# MAGI_sUSBMeter.net
KiCad netlist of a schematic drawn in Altium Designer
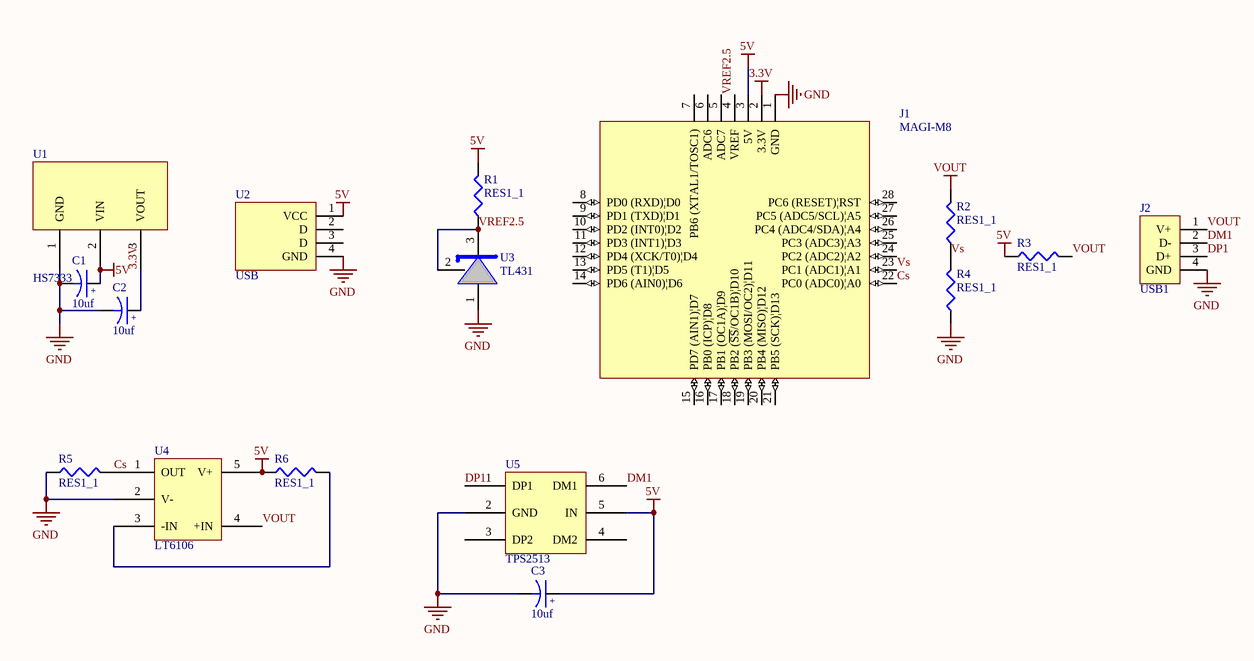
[diagram p0: MAGI'sUSBMeter.SchDoc]

(export (version "E")
  (design (tool "Eeschema 10.0.6"))
  (components
    (comp (ref "C1")
      (value "10uf")
      (footprint "6-0805_N")
      (description "Capacitor")
      (libsource (lib "电容器") (part "CAPACITOR POL"))
    )
    (comp (ref "C2")
      (value "10uf")
      (footprint "6-0805_N")
      (description "Capacitor")
      (libsource (lib "电容器") (part "CAPACITOR POL"))
    )
    (comp (ref "C3")
      (value "10uf")
      (footprint "6-0805_N")
      (description "Capacitor")
      (libsource (lib "电容器") (part "CAPACITOR POL"))
    )
    (comp (ref "J1") (value "MAGI-M8") (footprint "MAGI-M8") (libsource (lib "MAGI-M8") (part "MAGI-M8")))
    (comp (ref "J2") (value "USB1") (footprint "USB-04A") (libsource (lib "USB接口") (part "USB1")))
    (comp (ref "R1") (value "RES1_1") (footprint "6-0805_N") (libsource (lib "电阻器") (part "RES1_1")))
    (comp (ref "R2") (value "RES1_1") (footprint "6-0805_N") (libsource (lib "电阻器") (part "RES1_1")))
    (comp (ref "R3") (value "RES1_1") (footprint "2512") (libsource (lib "电阻器") (part "RES1_1")))
    (comp (ref "R4") (value "RES1_1") (footprint "6-0805_N") (libsource (lib "电阻器") (part "RES1_1")))
    (comp (ref "R5") (value "RES1_1") (footprint "6-0805_N") (libsource (lib "电阻器") (part "RES1_1")))
    (comp (ref "R6") (value "RES1_1") (footprint "6-0805_N") (libsource (lib "电阻器") (part "RES1_1")))
    (comp (ref "U1") (value "HS7333") (footprint "HS7333") (libsource (lib "PMIC") (part "HS7333")))
    (comp (ref "U2") (value "USB") (footprint "MicroUSB") (libsource (lib "USB接口") (part "USB")))
    (comp (ref "U3") (value "TL431") (footprint "SOT23_N") (libsource (lib "汇总") (part "TL431")))
    (comp (ref "U4") (value "LT6106") (footprint "LM2731") (libsource (lib "PMIC") (part "LT6106")))
    (comp (ref "U5") (value "TPS2513") (footprint "TPS2513") (libsource (lib "PMIC") (part "TPS2513")))
  )
  (nets
    (net (code "1") (name "/Cs") (class "Default")
      (node (ref "J1") (pin "22") (pinfunction "PC0_(ADC0)¦A0_22") (pintype "bidirectional"))
      (node (ref "R5") (pin "2") (pinfunction "2_2") (pintype "passive"))
      (node (ref "U4") (pin "1") (pinfunction "OUT_1") (pintype "passive"))
    )
    (net (code "2") (name "/DM1") (class "Default")
      (node (ref "J2") (pin "2") (pinfunction "D-_2") (pintype "passive"))
      (node (ref "U5") (pin "6") (pinfunction "DM1_6") (pintype "passive"))
    )
    (net (code "3") (name "/DP1") (class "Default")
      (node (ref "J2") (pin "3") (pinfunction "D+_3") (pintype "passive"))
      (node (ref "U5") (pin "1") (pinfunction "DP1_1") (pintype "passive"))
    )
    (net (code "4") (name "/VREF2.5") (class "Default")
      (node (ref "J1") (pin "4") (pinfunction "VREF_4") (pintype "passive"))
      (node (ref "R1") (pin "1") (pinfunction "1_1") (pintype "passive"))
      (node (ref "U3") (pin "2") (pinfunction "REF_2") (pintype "passive"))
      (node (ref "U3") (pin "3") (pinfunction "ANODE_3") (pintype "passive"))
    )
    (net (code "5") (name "/Vs") (class "Default")
      (node (ref "J1") (pin "23") (pinfunction "PC1_(ADC1)¦A1_23") (pintype "bidirectional"))
      (node (ref "R2") (pin "1") (pinfunction "1_1") (pintype "passive"))
      (node (ref "R4") (pin "2") (pinfunction "2_2") (pintype "passive"))
    )
    (net (code "6") (name "3.3V") (class "Default")
      (node (ref "C2") (pin "1") (pinfunction "1_1") (pintype "passive"))
      (node (ref "J1") (pin "2") (pinfunction "3.3V_2") (pintype "power_in"))
      (node (ref "U1") (pin "3") (pinfunction "VOUT_3") (pintype "passive"))
    )
    (net (code "7") (name "5V") (class "Default")
      (node (ref "C1") (pin "1") (pinfunction "1_1") (pintype "passive"))
      (node (ref "C3") (pin "1") (pinfunction "1_1") (pintype "passive"))
      (node (ref "J1") (pin "3") (pinfunction "5V_3") (pintype "power_in"))
      (node (ref "R1") (pin "2") (pinfunction "2_2") (pintype "passive"))
      (node (ref "R3") (pin "1") (pinfunction "1_1") (pintype "passive"))
      (node (ref "R6") (pin "1") (pinfunction "1_1") (pintype "passive"))
      (node (ref "U1") (pin "2") (pinfunction "VIN_2") (pintype "passive"))
      (node (ref "U2") (pin "1") (pinfunction "VCC_1") (pintype "passive"))
      (node (ref "U4") (pin "5") (pinfunction "V+_5") (pintype "passive"))
      (node (ref "U5") (pin "5") (pinfunction "IN_5") (pintype "passive"))
    )
    (net (code "8") (name "GND") (class "Default")
      (node (ref "C1") (pin "2") (pinfunction "2_2") (pintype "passive"))
      (node (ref "C2") (pin "2") (pinfunction "2_2") (pintype "passive"))
      (node (ref "C3") (pin "2") (pinfunction "2_2") (pintype "passive"))
      (node (ref "J1") (pin "1") (pinfunction "GND_1") (pintype "power_in"))
      (node (ref "J2") (pin "4") (pinfunction "GND_4") (pintype "passive"))
      (node (ref "R4") (pin "1") (pinfunction "1_1") (pintype "passive"))
      (node (ref "R5") (pin "1") (pinfunction "1_1") (pintype "passive"))
      (node (ref "U1") (pin "1") (pinfunction "GND_1") (pintype "passive"))
      (node (ref "U2") (pin "4") (pinfunction "GND_4") (pintype "passive"))
      (node (ref "U3") (pin "1") (pinfunction "CATHODE_1") (pintype "passive"))
      (node (ref "U4") (pin "2") (pinfunction "V-_2") (pintype "passive"))
      (node (ref "U5") (pin "2") (pinfunction "GND_2") (pintype "passive"))
    )
    (net (code "9") (name "Net-(U4--IN)") (class "Default")
      (node (ref "R6") (pin "2") (pinfunction "2_2") (pintype "passive"))
      (node (ref "U4") (pin "3") (pinfunction "-IN_3") (pintype "passive"))
    )
    (net (code "10") (name "VOUT") (class "Default")
      (node (ref "J2") (pin "1") (pinfunction "V+_1") (pintype "passive"))
      (node (ref "R2") (pin "2") (pinfunction "2_2") (pintype "passive"))
      (node (ref "R3") (pin "2") (pinfunction "2_2") (pintype "passive"))
      (node (ref "U4") (pin "4") (pinfunction "+IN_4") (pintype "passive"))
    )
    (net (code "11") (name "unconnected-(J1-ADC6-Pad6)") (class "Default")
      (node (ref "J1") (pin "6") (pinfunction "ADC6_6") (pintype "passive"))
    )
    (net (code "12") (name "unconnected-(J1-ADC7-Pad5)") (class "Default")
      (node (ref "J1") (pin "5") (pinfunction "ADC7_5") (pintype "passive"))
    )
    (net (code "13") (name "unconnected-(J1-PB0_(ICP)¦D8-Pad16)") (class "Default")
      (node (ref "J1") (pin "16") (pinfunction "PB0_(ICP)¦D8_16") (pintype "bidirectional"))
    )
    (net (code "14") (name "unconnected-(J1-PB1_(OC1A)¦D9-Pad17)") (class "Default")
      (node (ref "J1") (pin "17") (pinfunction "PB1_(OC1A)¦D9_17") (pintype "bidirectional"))
    )
    (net (code "15") (name "unconnected-(J1-PB2_(~{SS}{slash}OC1B)¦D10-Pad18)") (class "Default")
      (node (ref "J1") (pin "18") (pinfunction "PB2_(~{SS}/OC1B)¦D10_18") (pintype "bidirectional"))
    )
    (net (code "16") (name "unconnected-(J1-PB3_(MOSI{slash}OC2)¦D11-Pad19)") (class "Default")
      (node (ref "J1") (pin "19") (pinfunction "PB3_(MOSI/OC2)¦D11_19") (pintype "bidirectional"))
    )
    (net (code "17") (name "unconnected-(J1-PB4_(MISO)¦D12-Pad20)") (class "Default")
      (node (ref "J1") (pin "20") (pinfunction "PB4_(MISO)¦D12_20") (pintype "bidirectional"))
    )
    (net (code "18") (name "unconnected-(J1-PB5_(SCK)¦D13-Pad21)") (class "Default")
      (node (ref "J1") (pin "21") (pinfunction "PB5_(SCK)¦D13_21") (pintype "bidirectional"))
    )
    (net (code "19") (name "unconnected-(J1-PB6_(XTAL1{slash}TOSC1)-Pad7)") (class "Default")
      (node (ref "J1") (pin "7") (pinfunction "PB6_(XTAL1/TOSC1)_7") (pintype "passive"))
    )
    (net (code "20") (name "unconnected-(J1-PC2_(ADC2)¦A2-Pad24)") (class "Default")
      (node (ref "J1") (pin "24") (pinfunction "PC2_(ADC2)¦A2_24") (pintype "bidirectional"))
    )
    (net (code "21") (name "unconnected-(J1-PC3_(ADC3)¦A3-Pad25)") (class "Default")
      (node (ref "J1") (pin "25") (pinfunction "PC3_(ADC3)¦A3_25") (pintype "bidirectional"))
    )
    (net (code "22") (name "unconnected-(J1-PC4_(ADC4{slash}SDA)¦A4-Pad26)") (class "Default")
      (node (ref "J1") (pin "26") (pinfunction "PC4_(ADC4/SDA)¦A4_26") (pintype "bidirectional"))
    )
    (net (code "23") (name "unconnected-(J1-PC5_(ADC5{slash}SCL)¦A5-Pad27)") (class "Default")
      (node (ref "J1") (pin "27") (pinfunction "PC5_(ADC5/SCL)¦A5_27") (pintype "bidirectional"))
    )
    (net (code "24") (name "unconnected-(J1-PC6_(RESET)¦RST-Pad28)") (class "Default")
      (node (ref "J1") (pin "28") (pinfunction "PC6_(RESET)¦RST_28") (pintype "bidirectional"))
    )
    (net (code "25") (name "unconnected-(J1-PD0_(RXD)¦D0-Pad8)") (class "Default")
      (node (ref "J1") (pin "8") (pinfunction "PD0_(RXD)¦D0_8") (pintype "bidirectional"))
    )
    (net (code "26") (name "unconnected-(J1-PD1_(TXD)¦D1-Pad9)") (class "Default")
      (node (ref "J1") (pin "9") (pinfunction "PD1_(TXD)¦D1_9") (pintype "bidirectional"))
    )
    (net (code "27") (name "unconnected-(J1-PD2_(INT0)¦D2-Pad10)") (class "Default")
      (node (ref "J1") (pin "10") (pinfunction "PD2_(INT0)¦D2_10") (pintype "bidirectional"))
    )
    (net (code "28") (name "unconnected-(J1-PD3_(INT1)¦D3-Pad11)") (class "Default")
      (node (ref "J1") (pin "11") (pinfunction "PD3_(INT1)¦D3_11") (pintype "bidirectional"))
    )
    (net (code "29") (name "unconnected-(J1-PD4_(XCK{slash}T0)¦D4-Pad12)") (class "Default")
      (node (ref "J1") (pin "12") (pinfunction "PD4_(XCK/T0)¦D4_12") (pintype "bidirectional"))
    )
    (net (code "30") (name "unconnected-(J1-PD5_(T1)¦D5-Pad13)") (class "Default")
      (node (ref "J1") (pin "13") (pinfunction "PD5_(T1)¦D5_13") (pintype "bidirectional"))
    )
    (net (code "31") (name "unconnected-(J1-PD6_(AIN0)¦D6-Pad14)") (class "Default")
      (node (ref "J1") (pin "14") (pinfunction "PD6_(AIN0)¦D6_14") (pintype "bidirectional"))
    )
    (net (code "32") (name "unconnected-(J1-PD7_(AIN1)¦D7-Pad15)") (class "Default")
      (node (ref "J1") (pin "15") (pinfunction "PD7_(AIN1)¦D7_15") (pintype "bidirectional"))
    )
    (net (code "33") (name "unconnected-(U2-D-Pad2)") (class "Default")
      (node (ref "U2") (pin "2") (pinfunction "D_2") (pintype "passive"))
    )
    (net (code "34") (name "unconnected-(U2-D-Pad3)") (class "Default")
      (node (ref "U2") (pin "3") (pinfunction "D_3") (pintype "passive"))
    )
    (net (code "35") (name "unconnected-(U5-DM2-Pad4)") (class "Default")
      (node (ref "U5") (pin "4") (pinfunction "DM2_4") (pintype "passive"))
    )
    (net (code "36") (name "unconnected-(U5-DP2-Pad3)") (class "Default")
      (node (ref "U5") (pin "3") (pinfunction "DP2_3") (pintype "passive"))
    )
  )
)
